# 17_CAN_BUS.net
KiCad netlist of a schematic drawn in Altium Designer
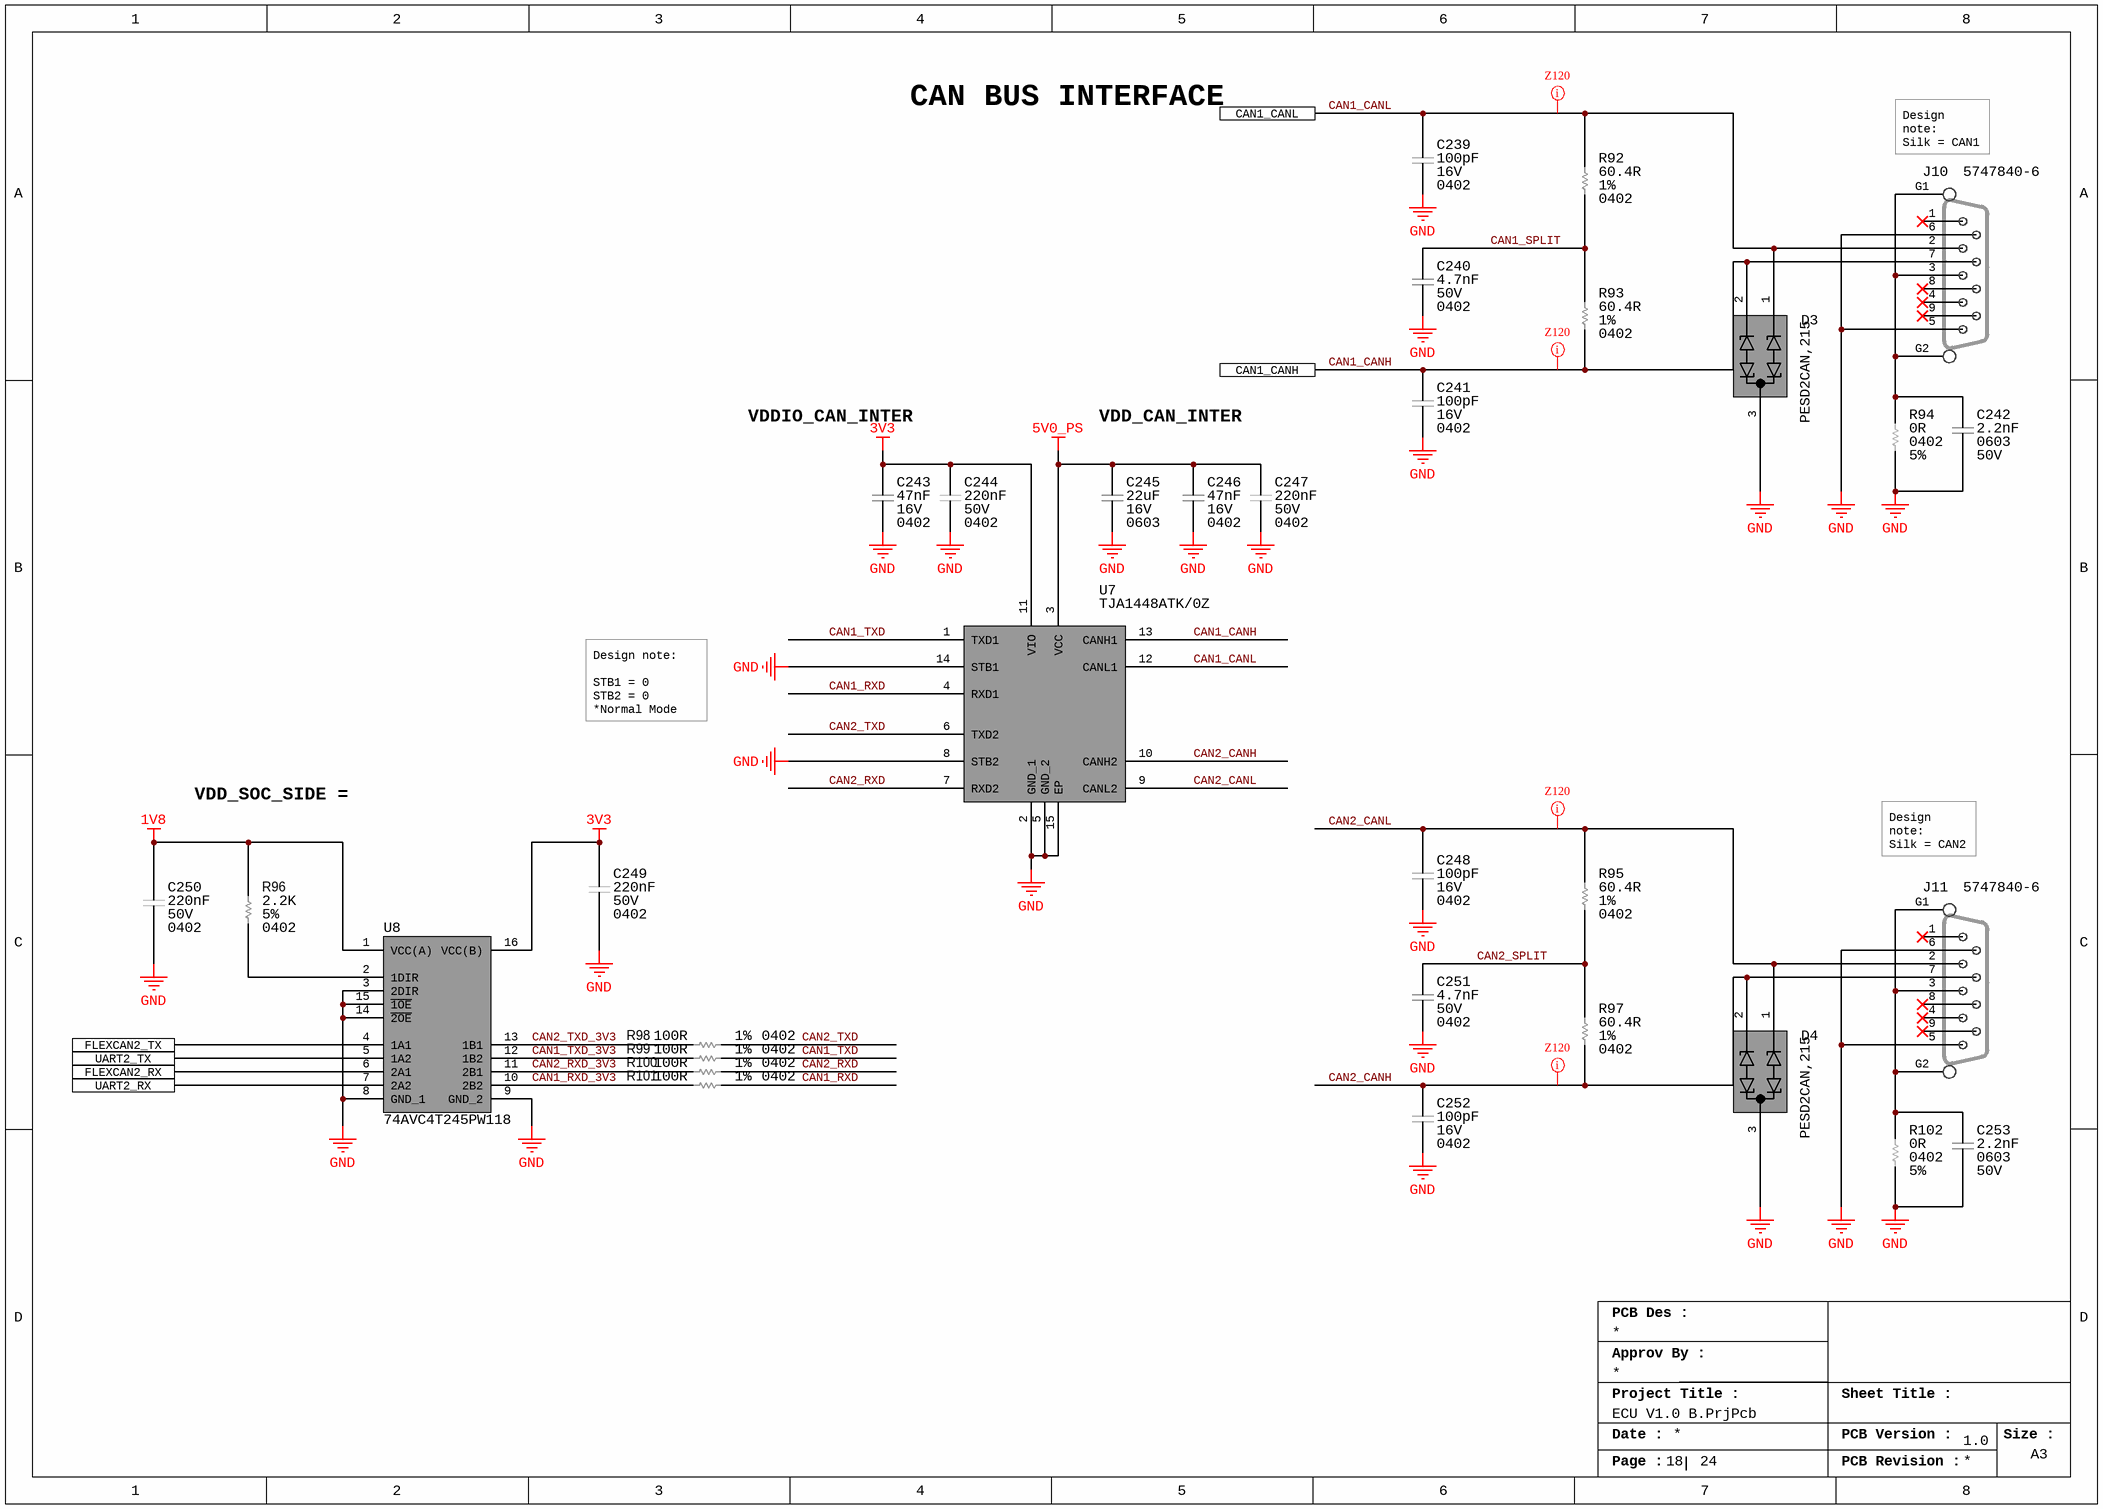
[diagram p0: 17_CAN_BUS.SchDoc]

(export (version "E")
  (design (tool "Eeschema 10.0.6"))
  (components
    (comp (ref "C239")
      (value "CC0402JRNPO7BN101")
      (footprint "CAP_0402_CAPC1005X05N")
      (description "0402 100 pF 16 V ±5 % Tolerance NP0 SMT Multilayer Ceramic Capacitor")
      (fields
        (field (name "MANUFACTURER") "Yageo")
        (field (name "TOLERANCE") "5%")
        (field (name "VOLTAGE RATING (DC)") "16V")
        (field (name "CAPACITANCE") "100pF")
        (field (name "CASE/PACKAGE") "0402")
      )
      (libsource (lib "Electronic Devices_LIB") (part "CAP_100PF_16V_NP0_0402"))
    )
    (comp (ref "C240")
      (value "GRM155R61H472KA01D")
      (footprint "CAP_0402_CAPC1005X05N")
      (description "Multilayer Ceramic Capacitor, 100 uF, 16 V, ± 20%, X5R, 1210 [3225 Metric]")
      (fields
        (field (name "MANUFACTURER") "Murata")
        (field (name "TOLERANCE") "10%")
        (field (name "VOLTAGE RATING") "50V")
        (field (name "CAPACITANCE") "4.7nF")
        (field (name "CASE/PACKAGE") "0402")
      )
      (libsource (lib "Electronic Devices_LIB") (part "CAP_4700PF_50V_X5R_0402"))
    )
    (comp (ref "C241")
      (value "CC0402JRNPO7BN101")
      (footprint "CAP_0402_CAPC1005X05N")
      (description "0402 100 pF 16 V ±5 % Tolerance NP0 SMT Multilayer Ceramic Capacitor")
      (fields
        (field (name "MANUFACTURER") "Yageo")
        (field (name "TOLERANCE") "5%")
        (field (name "VOLTAGE RATING (DC)") "16V")
        (field (name "CAPACITANCE") "100pF")
        (field (name "CASE/PACKAGE") "0402")
      )
      (libsource (lib "Electronic Devices_LIB") (part "CAP_100PF_16V_NP0_0402"))
    )
    (comp (ref "C242")
      (value "GRM1885C1H222JA01D")
      (footprint "CAP_0603_CAPC1608X08N")
      (description "Multilayer Ceramic Capacitor, 2200 pF, 50 V, ï¿½ 5%, C0G (NP0), 0603 [1608 Metric]")
      (fields
        (field (name "MANUFACTURER") "Murata")
        (field (name "TOLERANCE") "5%")
        (field (name "CASE/PACKAGE") "0603")
        (field (name "VOLTAGE RATING") "50V")
        (field (name "CAPACITANCE") "2.2nF")
      )
      (libsource (lib "Electronic Devices_LIB") (part "CAP_2.2nF_50V_NP0_0402"))
    )
    (comp (ref "C243")
      (value "GCM155R71C473KA37D")
      (footprint "CAP_0402_CAPC1005X05N")
      (description "Multilayer Ceramic Capacitor, 0.047 uF, 16 V, ± 10%, X7R, 0402 [1005 Metric]")
      (fields
        (field (name "MANUFACTURER") "Murata")
        (field (name "TOLERANCE") "10%")
        (field (name "CAPACITANCE") "47nF")
        (field (name "VOLTAGE RATING") "16V")
        (field (name "CASE/PACKAGE") "0402")
      )
      (libsource (lib "Electronic Devices_LIB") (part "CAP_47nF_16V_X7R_0402"))
    )
    (comp (ref "C244")
      (value "GRM155R61H224KE01W")
      (footprint "CAP_0402_CAPC1005X05N")
      (description "Multilayer Ceramic Capacitor, 0.22 uF, 50 VDC, ± 10%, X5R, 0402 [1005 Metric]")
      (fields
        (field (name "MANUFACTURER") "Murata")
        (field (name "CASE/PACKAGE") "0402")
        (field (name "VOLTAGE RATING (DC)") "50V")
        (field (name "CAPACITANCE") "220nF")
      )
      (libsource (lib "Electronic Devices_LIB") (part "CAP_0.22UF_50V_X5R_0402"))
    )
    (comp (ref "C245")
      (value "CL10A226MO7JZNC")
      (footprint "CAP_0603_CAPC1608X08N")
      (description "Cap Ceramic 22uF 16V X5R 20% Pad SMD 0603 85C T/R")
      (fields
        (field (name "MANUFACTURER") "Samsung")
        (field (name "TOLERANCE") "20%")
        (field (name "CAPACITANCE") "22uF")
        (field (name "VOLTAGE RATING") "16V")
        (field (name "CASE/PACKAGE") "0603")
      )
      (libsource (lib "Electronic Devices_LIB") (part "CAP_22UF_16V_X5R_0603"))
    )
    (comp (ref "C246")
      (value "GCM155R71C473KA37D")
      (footprint "CAP_0402_CAPC1005X05N")
      (description "Multilayer Ceramic Capacitor, 0.047 uF, 16 V, ± 10%, X7R, 0402 [1005 Metric]")
      (fields
        (field (name "MANUFACTURER") "Murata")
        (field (name "TOLERANCE") "10%")
        (field (name "CAPACITANCE") "47nF")
        (field (name "VOLTAGE RATING") "16V")
        (field (name "CASE/PACKAGE") "0402")
      )
      (libsource (lib "Electronic Devices_LIB") (part "CAP_47nF_16V_X7R_0402"))
    )
    (comp (ref "C247")
      (value "GRM155R61H224KE01W")
      (footprint "CAP_0402_CAPC1005X05N")
      (description "Multilayer Ceramic Capacitor, 0.22 uF, 50 VDC, ± 10%, X5R, 0402 [1005 Metric]")
      (fields
        (field (name "MANUFACTURER") "Murata")
        (field (name "CASE/PACKAGE") "0402")
        (field (name "VOLTAGE RATING (DC)") "50V")
        (field (name "CAPACITANCE") "220nF")
      )
      (libsource (lib "Electronic Devices_LIB") (part "CAP_0.22UF_50V_X5R_0402"))
    )
    (comp (ref "C248")
      (value "CC0402JRNPO7BN101")
      (footprint "CAP_0402_CAPC1005X05N")
      (description "0402 100 pF 16 V ±5 % Tolerance NP0 SMT Multilayer Ceramic Capacitor")
      (fields
        (field (name "MANUFACTURER") "Yageo")
        (field (name "TOLERANCE") "5%")
        (field (name "VOLTAGE RATING (DC)") "16V")
        (field (name "CAPACITANCE") "100pF")
        (field (name "CASE/PACKAGE") "0402")
      )
      (libsource (lib "Electronic Devices_LIB") (part "CAP_100PF_16V_NP0_0402"))
    )
    (comp (ref "C249")
      (value "GRM155R61H224KE01W")
      (footprint "CAP_0402_CAPC1005X05N")
      (description "Multilayer Ceramic Capacitor, 0.22 uF, 50 VDC, ± 10%, X5R, 0402 [1005 Metric]")
      (fields
        (field (name "MANUFACTURER") "Murata")
        (field (name "CASE/PACKAGE") "0402")
        (field (name "VOLTAGE RATING (DC)") "50V")
        (field (name "CAPACITANCE") "220nF")
      )
      (libsource (lib "Electronic Devices_LIB") (part "CAP_0.22UF_50V_X5R_0402"))
    )
    (comp (ref "C250")
      (value "GRM155R61H224KE01W")
      (footprint "CAP_0402_CAPC1005X05N")
      (description "Multilayer Ceramic Capacitor, 0.22 uF, 50 VDC, ± 10%, X5R, 0402 [1005 Metric]")
      (fields
        (field (name "MANUFACTURER") "Murata")
        (field (name "CASE/PACKAGE") "0402")
        (field (name "VOLTAGE RATING (DC)") "50V")
        (field (name "CAPACITANCE") "220nF")
      )
      (libsource (lib "Electronic Devices_LIB") (part "CAP_0.22UF_50V_X5R_0402"))
    )
    (comp (ref "C251")
      (value "GRM155R61H472KA01D")
      (footprint "CAP_0402_CAPC1005X05N")
      (description "Multilayer Ceramic Capacitor, 100 uF, 16 V, ± 20%, X5R, 1210 [3225 Metric]")
      (fields
        (field (name "MANUFACTURER") "Murata")
        (field (name "TOLERANCE") "10%")
        (field (name "VOLTAGE RATING") "50V")
        (field (name "CAPACITANCE") "4.7nF")
        (field (name "CASE/PACKAGE") "0402")
      )
      (libsource (lib "Electronic Devices_LIB") (part "CAP_4700PF_50V_X5R_0402"))
    )
    (comp (ref "C252")
      (value "CC0402JRNPO7BN101")
      (footprint "CAP_0402_CAPC1005X05N")
      (description "0402 100 pF 16 V ±5 % Tolerance NP0 SMT Multilayer Ceramic Capacitor")
      (fields
        (field (name "MANUFACTURER") "Yageo")
        (field (name "TOLERANCE") "5%")
        (field (name "VOLTAGE RATING (DC)") "16V")
        (field (name "CAPACITANCE") "100pF")
        (field (name "CASE/PACKAGE") "0402")
      )
      (libsource (lib "Electronic Devices_LIB") (part "CAP_100PF_16V_NP0_0402"))
    )
    (comp (ref "C253")
      (value "GRM1885C1H222JA01D")
      (footprint "CAP_0603_CAPC1608X08N")
      (description "Multilayer Ceramic Capacitor, 2200 pF, 50 V, ï¿½ 5%, C0G (NP0), 0603 [1608 Metric]")
      (fields
        (field (name "MANUFACTURER") "Murata")
        (field (name "TOLERANCE") "5%")
        (field (name "CASE/PACKAGE") "0603")
        (field (name "VOLTAGE RATING") "50V")
        (field (name "CAPACITANCE") "2.2nF")
      )
      (libsource (lib "Electronic Devices_LIB") (part "CAP_2.2nF_50V_NP0_0402"))
    )
    (comp (ref "D3")
      (value "PESD2CAN,215")
      (footprint "DIO_PESD2CAN,215")
      (description "5A 230W 41V 26.2V Bidirectional 24V SOT-23 ESD and Surge Protection (TVS/ESD) ROHS")
      (fields (field (name "MANUFACTURER") "Nexperia"))
      (libsource (lib "Electronic Devices_LIB") (part "DIO_TVS_41V_5A_PESD2CAN,215"))
    )
    (comp (ref "D4")
      (value "PESD2CAN,215")
      (footprint "DIO_PESD2CAN,215")
      (description "5A 230W 41V 26.2V Bidirectional 24V SOT-23 ESD and Surge Protection (TVS/ESD) ROHS")
      (fields (field (name "MANUFACTURER") "Nexperia"))
      (libsource (lib "Electronic Devices_LIB") (part "DIO_TVS_41V_5A_PESD2CAN,215"))
    )
    (comp (ref "J10")
      (value "5747840-6")
      (footprint "TE_5747840-6")
      (description "D Subminiature Connector, 9 Contact(s), Male, 0.108 inch Pitch, Solder Terminal, #4-40, Plug")
      (fields (field (name "MANUFACTURER") "TE Connectivity"))
      (libsource (lib "Electronic Devices_LIB") (part "CONN_DB9_TEConnectivity_5747840-6"))
    )
    (comp (ref "J11")
      (value "5747840-6")
      (footprint "TE_5747840-6")
      (description "D Subminiature Connector, 9 Contact(s), Male, 0.108 inch Pitch, Solder Terminal, #4-40, Plug")
      (fields (field (name "MANUFACTURER") "TE Connectivity"))
      (libsource (lib "Electronic Devices_LIB") (part "CONN_DB9_TEConnectivity_5747840-6"))
    )
    (comp (ref "R92")
      (value "RK73H1ETTP60R4F")
      (footprint "RES_0402_RESC1005X04N")
      (description "Res Thick Film 0402 60.4 Ohm 1% 0.1W(1/10W) ±100ppm/C Pad SMD Automotive T/R")
      (fields
        (field (name "MANUFACTURER") "KOA Speer")
        (field (name "TOLERANCE") "1%")
        (field (name "RESISTANCE") "60.4R")
        (field (name "CASE/PACKAGE") "0402")
      )
      (libsource (lib "Electronic Devices_LIB") (part "RES_60.4R_1%_100mW_0402"))
    )
    (comp (ref "R93")
      (value "RK73H1ETTP60R4F")
      (footprint "RES_0402_RESC1005X04N")
      (description "Res Thick Film 0402 60.4 Ohm 1% 0.1W(1/10W) ±100ppm/C Pad SMD Automotive T/R")
      (fields
        (field (name "MANUFACTURER") "KOA Speer")
        (field (name "TOLERANCE") "1%")
        (field (name "RESISTANCE") "60.4R")
        (field (name "CASE/PACKAGE") "0402")
      )
      (libsource (lib "Electronic Devices_LIB") (part "RES_60.4R_1%_100mW_0402"))
    )
    (comp (ref "R94")
      (value "ERJ-2GE0R00X")
      (footprint "RES_0402_RESC1005X04N")
      (description "SMD Chip Resistor, Jumper, 0 ohm, 100 mW, 0402 [1005 Metric], Thick Film, General Purpose")
      (fields
        (field (name "MANUFACTURER") "Panasonic")
        (field (name "CASE CODE (IMPERIAL)") "0402")
        (field (name "TOLERANCE") "5%")
        (field (name "RESISTANCE") "0R")
      )
      (libsource (lib "Electronic Devices_LIB") (part "RES_0R_5%_100mW_0402"))
    )
    (comp (ref "R95")
      (value "RK73H1ETTP60R4F")
      (footprint "RES_0402_RESC1005X04N")
      (description "Res Thick Film 0402 60.4 Ohm 1% 0.1W(1/10W) ±100ppm/C Pad SMD Automotive T/R")
      (fields
        (field (name "MANUFACTURER") "KOA Speer")
        (field (name "TOLERANCE") "1%")
        (field (name "RESISTANCE") "60.4R")
        (field (name "CASE/PACKAGE") "0402")
      )
      (libsource (lib "Electronic Devices_LIB") (part "RES_60.4R_1%_100mW_0402"))
    )
    (comp (ref "R96")
      (value "RC0402JR-072K2L")
      (footprint "RES_0402_RESC1005X04N")
      (description "SMD Chip Resistor, 2.2 kOhm, ± 5%, 63 mW, 0402 [1005 Metric], Thick Film, General Purpose")
      (fields
        (field (name "MANUFACTURER") "Yageo")
        (field (name "TOLERANCE") "5%")
        (field (name "RESISTANCE") "2.2K")
        (field (name "CASE/PACKAGE") "0402")
      )
      (libsource (lib "Electronic Devices_LIB") (part "RES_2.2K_5%_63mW_0402"))
    )
    (comp (ref "R97")
      (value "RK73H1ETTP60R4F")
      (footprint "RES_0402_RESC1005X04N")
      (description "Res Thick Film 0402 60.4 Ohm 1% 0.1W(1/10W) ±100ppm/C Pad SMD Automotive T/R")
      (fields
        (field (name "MANUFACTURER") "KOA Speer")
        (field (name "TOLERANCE") "1%")
        (field (name "RESISTANCE") "60.4R")
        (field (name "CASE/PACKAGE") "0402")
      )
      (libsource (lib "Electronic Devices_LIB") (part "RES_60.4R_1%_100mW_0402"))
    )
    (comp (ref "R98")
      (value "ERJ-2RKF1000X")
      (footprint "RES_0402_RESC1005X04N")
      (description "Resistor Thick Film 0402 100 Ohm 1% 1/10W 100ppm/C Molded SMD Punched Carrier T/R")
      (fields
        (field (name "MANUFACTURER") "Panasonic")
        (field (name "TOLERANCE") "1%")
        (field (name "RESISTANCE") "100R")
        (field (name "CASE/PACKAGE") "0402")
      )
      (libsource (lib "Electronic Devices_LIB") (part "RES_100R_1%_100mW_0402"))
    )
    (comp (ref "R99")
      (value "ERJ-2RKF1000X")
      (footprint "RES_0402_RESC1005X04N")
      (description "Resistor Thick Film 0402 100 Ohm 1% 1/10W 100ppm/C Molded SMD Punched Carrier T/R")
      (fields
        (field (name "MANUFACTURER") "Panasonic")
        (field (name "TOLERANCE") "1%")
        (field (name "RESISTANCE") "100R")
        (field (name "CASE/PACKAGE") "0402")
      )
      (libsource (lib "Electronic Devices_LIB") (part "RES_100R_1%_100mW_0402"))
    )
    (comp (ref "R100")
      (value "ERJ-2RKF1000X")
      (footprint "RES_0402_RESC1005X04N")
      (description "Resistor Thick Film 0402 100 Ohm 1% 1/10W 100ppm/C Molded SMD Punched Carrier T/R")
      (fields
        (field (name "MANUFACTURER") "Panasonic")
        (field (name "TOLERANCE") "1%")
        (field (name "RESISTANCE") "100R")
        (field (name "CASE/PACKAGE") "0402")
      )
      (libsource (lib "Electronic Devices_LIB") (part "RES_100R_1%_100mW_0402"))
    )
    (comp (ref "R101")
      (value "ERJ-2RKF1000X")
      (footprint "RES_0402_RESC1005X04N")
      (description "Resistor Thick Film 0402 100 Ohm 1% 1/10W 100ppm/C Molded SMD Punched Carrier T/R")
      (fields
        (field (name "MANUFACTURER") "Panasonic")
        (field (name "TOLERANCE") "1%")
        (field (name "RESISTANCE") "100R")
        (field (name "CASE/PACKAGE") "0402")
      )
      (libsource (lib "Electronic Devices_LIB") (part "RES_100R_1%_100mW_0402"))
    )
    (comp (ref "R102")
      (value "ERJ-2GE0R00X")
      (footprint "RES_0402_RESC1005X04N")
      (description "SMD Chip Resistor, Jumper, 0 ohm, 100 mW, 0402 [1005 Metric], Thick Film, General Purpose")
      (fields
        (field (name "MANUFACTURER") "Panasonic")
        (field (name "CASE CODE (IMPERIAL)") "0402")
        (field (name "TOLERANCE") "5%")
        (field (name "RESISTANCE") "0R")
      )
      (libsource (lib "Electronic Devices_LIB") (part "RES_0R_5%_100mW_0402"))
    )
    (comp (ref "U7")
      (value "TJA1448ATK/0Z")
      (footprint "SON65P300X450X100-15N")
      (description "Can Transceiver with Standby Mode Dual High-Speed 5Mbps 4.5V to 5.5V 14-Pin HVSON")
      (fields (field (name "MANUFACTURER") "NXP Semiconductors"))
      (libsource (lib "Electronic Devices_LIB") (part "IC_TRANSCEIVER_CAN_TJA1448ATK/0Z"))
    )
    (comp (ref "U8")
      (value "74AVC4T245PW118")
      (footprint "SOP65P640X110-16N")
      (description "74Avc4T245Pw/Sot403/Tssop16 Rohs Compliant: Yes ¦Nexperia 74AVC4T245PW 118")
      (fields (field (name "MANUFACTURER") "Nexperia"))
      (libsource (lib "Electronic Devices_LIB") (part "IC_TRANSLATION_TXRX_74AVC4T245PW118"))
    )
  )
  (nets
    (net (code "1") (name "/CAN1_CANH") (class "Default")
      (node (ref "C241") (pin "2") (pinfunction "2_2") (pintype "passive"))
      (node (ref "D3") (pin "2") (pinfunction "C2_2") (pintype "passive"))
      (node (ref "J10") (pin "7") (pinfunction "7_7") (pintype "passive"))
      (node (ref "R93") (pin "1") (pinfunction "1_1") (pintype "passive"))
      (node (ref "U7") (pin "13") (pinfunction "CANH1_13") (pintype "passive"))
    )
    (net (code "2") (name "/CAN1_CANL") (class "Default")
      (node (ref "C239") (pin "2") (pinfunction "2_2") (pintype "passive"))
      (node (ref "D3") (pin "1") (pinfunction "C1_1") (pintype "passive"))
      (node (ref "J10") (pin "2") (pinfunction "2_2") (pintype "passive"))
      (node (ref "R92") (pin "2") (pinfunction "2_2") (pintype "passive"))
      (node (ref "U7") (pin "12") (pinfunction "CANL1_12") (pintype "passive"))
    )
    (net (code "3") (name "/CAN1_RXD") (class "Default")
      (node (ref "R101") (pin "2") (pinfunction "2_2") (pintype "passive"))
      (node (ref "U7") (pin "4") (pinfunction "RXD1_4") (pintype "passive"))
    )
    (net (code "4") (name "/CAN1_RXD_3V3") (class "Default")
      (node (ref "R101") (pin "1") (pinfunction "1_1") (pintype "passive"))
      (node (ref "U8") (pin "10") (pinfunction "2B2_10") (pintype "passive"))
    )
    (net (code "5") (name "/CAN1_SPLIT") (class "Default")
      (node (ref "C240") (pin "2") (pinfunction "2_2") (pintype "passive"))
      (node (ref "R92") (pin "1") (pinfunction "1_1") (pintype "passive"))
      (node (ref "R93") (pin "2") (pinfunction "2_2") (pintype "passive"))
    )
    (net (code "6") (name "/CAN1_TXD") (class "Default")
      (node (ref "R99") (pin "2") (pinfunction "2_2") (pintype "passive"))
      (node (ref "U7") (pin "1") (pinfunction "TXD1_1") (pintype "passive"))
    )
    (net (code "7") (name "/CAN1_TXD_3V3") (class "Default")
      (node (ref "R99") (pin "1") (pinfunction "1_1") (pintype "passive"))
      (node (ref "U8") (pin "12") (pinfunction "1B2_12") (pintype "passive"))
    )
    (net (code "8") (name "/CAN2_CANH") (class "Default")
      (node (ref "C252") (pin "2") (pinfunction "2_2") (pintype "passive"))
      (node (ref "D4") (pin "2") (pinfunction "C2_2") (pintype "passive"))
      (node (ref "J11") (pin "7") (pinfunction "7_7") (pintype "passive"))
      (node (ref "R97") (pin "1") (pinfunction "1_1") (pintype "passive"))
      (node (ref "U7") (pin "10") (pinfunction "CANH2_10") (pintype "passive"))
    )
    (net (code "9") (name "/CAN2_CANL") (class "Default")
      (node (ref "C248") (pin "2") (pinfunction "2_2") (pintype "passive"))
      (node (ref "D4") (pin "1") (pinfunction "C1_1") (pintype "passive"))
      (node (ref "J11") (pin "2") (pinfunction "2_2") (pintype "passive"))
      (node (ref "R95") (pin "2") (pinfunction "2_2") (pintype "passive"))
      (node (ref "U7") (pin "9") (pinfunction "CANL2_9") (pintype "passive"))
    )
    (net (code "10") (name "/CAN2_RXD") (class "Default")
      (node (ref "R100") (pin "2") (pinfunction "2_2") (pintype "passive"))
      (node (ref "U7") (pin "7") (pinfunction "RXD2_7") (pintype "passive"))
    )
    (net (code "11") (name "/CAN2_RXD_3V3") (class "Default")
      (node (ref "R100") (pin "1") (pinfunction "1_1") (pintype "passive"))
      (node (ref "U8") (pin "11") (pinfunction "2B1_11") (pintype "passive"))
    )
    (net (code "12") (name "/CAN2_SPLIT") (class "Default")
      (node (ref "C251") (pin "2") (pinfunction "2_2") (pintype "passive"))
      (node (ref "R95") (pin "1") (pinfunction "1_1") (pintype "passive"))
      (node (ref "R97") (pin "2") (pinfunction "2_2") (pintype "passive"))
    )
    (net (code "13") (name "/CAN2_TXD") (class "Default")
      (node (ref "R98") (pin "2") (pinfunction "2_2") (pintype "passive"))
      (node (ref "U7") (pin "6") (pinfunction "TXD2_6") (pintype "passive"))
    )
    (net (code "14") (name "/CAN2_TXD_3V3") (class "Default")
      (node (ref "R98") (pin "1") (pinfunction "1_1") (pintype "passive"))
      (node (ref "U8") (pin "13") (pinfunction "1B1_13") (pintype "passive"))
    )
    (net (code "15") (name "/FLEXCAN2_RX") (class "Default")
      (node (ref "U8") (pin "6") (pinfunction "2A1_6") (pintype "passive"))
    )
    (net (code "16") (name "/FLEXCAN2_TX") (class "Default")
      (node (ref "U8") (pin "4") (pinfunction "1A1_4") (pintype "passive"))
    )
    (net (code "17") (name "/UART2_RX") (class "Default")
      (node (ref "U8") (pin "7") (pinfunction "2A2_7") (pintype "passive"))
    )
    (net (code "18") (name "/UART2_TX") (class "Default")
      (node (ref "U8") (pin "5") (pinfunction "1A2_5") (pintype "passive"))
    )
    (net (code "19") (name "1V8") (class "Default")
      (node (ref "C250") (pin "2") (pinfunction "2_2") (pintype "passive"))
      (node (ref "R96") (pin "2") (pinfunction "2_2") (pintype "passive"))
      (node (ref "U8") (pin "1") (pinfunction "VCC(A)_1") (pintype "passive"))
    )
    (net (code "20") (name "3V3") (class "Default")
      (node (ref "C243") (pin "2") (pinfunction "2_2") (pintype "passive"))
      (node (ref "C244") (pin "1") (pinfunction "1_1") (pintype "passive"))
      (node (ref "C249") (pin "2") (pinfunction "2_2") (pintype "passive"))
      (node (ref "U7") (pin "11") (pinfunction "VIO_11") (pintype "passive"))
      (node (ref "U8") (pin "16") (pinfunction "VCC(B)_16") (pintype "passive"))
    )
    (net (code "21") (name "5V0_PS") (class "Default")
      (node (ref "C245") (pin "2") (pinfunction "2_2") (pintype "passive"))
      (node (ref "C246") (pin "2") (pinfunction "2_2") (pintype "passive"))
      (node (ref "C247") (pin "1") (pinfunction "1_1") (pintype "passive"))
      (node (ref "U7") (pin "3") (pinfunction "VCC_3") (pintype "passive"))
    )
    (net (code "22") (name "GND") (class "Default")
      (node (ref "C239") (pin "1") (pinfunction "1_1") (pintype "passive"))
      (node (ref "C240") (pin "1") (pinfunction "1_1") (pintype "passive"))
      (node (ref "C241") (pin "1") (pinfunction "1_1") (pintype "passive"))
      (node (ref "C242") (pin "1") (pinfunction "1_1") (pintype "passive"))
      (node (ref "C243") (pin "1") (pinfunction "1_1") (pintype "passive"))
      (node (ref "C244") (pin "2") (pinfunction "2_2") (pintype "passive"))
      (node (ref "C245") (pin "1") (pinfunction "1_1") (pintype "passive"))
      (node (ref "C246") (pin "1") (pinfunction "1_1") (pintype "passive"))
      (node (ref "C247") (pin "2") (pinfunction "2_2") (pintype "passive"))
      (node (ref "C248") (pin "1") (pinfunction "1_1") (pintype "passive"))
      (node (ref "C249") (pin "1") (pinfunction "1_1") (pintype "passive"))
      (node (ref "C250") (pin "1") (pinfunction "1_1") (pintype "passive"))
      (node (ref "C251") (pin "1") (pinfunction "1_1") (pintype "passive"))
      (node (ref "C252") (pin "1") (pinfunction "1_1") (pintype "passive"))
      (node (ref "C253") (pin "1") (pinfunction "1_1") (pintype "passive"))
      (node (ref "D3") (pin "3") (pinfunction "CC_3") (pintype "passive"))
      (node (ref "D4") (pin "3") (pinfunction "CC_3") (pintype "passive"))
      (node (ref "J10") (pin "5") (pinfunction "5_5") (pintype "passive"))
      (node (ref "J10") (pin "6") (pinfunction "6_6") (pintype "passive"))
      (node (ref "J11") (pin "5") (pinfunction "5_5") (pintype "passive"))
      (node (ref "J11") (pin "6") (pinfunction "6_6") (pintype "passive"))
      (node (ref "R102") (pin "1") (pinfunction "1_1") (pintype "passive"))
      (node (ref "R94") (pin "1") (pinfunction "1_1") (pintype "passive"))
      (node (ref "U7") (pin "14") (pinfunction "STB1_14") (pintype "passive"))
      (node (ref "U7") (pin "15") (pinfunction "EP_15") (pintype "passive"))
      (node (ref "U7") (pin "2") (pinfunction "GND_1_2") (pintype "passive"))
      (node (ref "U7") (pin "5") (pinfunction "GND_2_5") (pintype "passive"))
      (node (ref "U7") (pin "8") (pinfunction "STB2_8") (pintype "passive"))
      (node (ref "U8") (pin "14") (pinfunction "~{2OE}_14") (pintype "passive"))
      (node (ref "U8") (pin "15") (pinfunction "~{1OE}_15") (pintype "passive"))
      (node (ref "U8") (pin "3") (pinfunction "2DIR_3") (pintype "passive"))
      (node (ref "U8") (pin "8") (pinfunction "GND_1_8") (pintype "passive"))
      (node (ref "U8") (pin "9") (pinfunction "GND_2_9") (pintype "passive"))
    )
    (net (code "23") (name "Net-(J10-G)") (class "Default")
      (node (ref "C242") (pin "2") (pinfunction "2_2") (pintype "passive"))
      (node (ref "J10") (pin "3") (pinfunction "3_3") (pintype "passive"))
      (node (ref "J10") (pin "G1") (pinfunction "G1_G1") (pintype "passive"))
      (node (ref "J10") (pin "G2") (pinfunction "G_G2") (pintype "passive"))
      (node (ref "R94") (pin "2") (pinfunction "2_2") (pintype "passive"))
    )
    (net (code "24") (name "Net-(J11-G)") (class "Default")
      (node (ref "C253") (pin "2") (pinfunction "2_2") (pintype "passive"))
      (node (ref "J11") (pin "3") (pinfunction "3_3") (pintype "passive"))
      (node (ref "J11") (pin "G1") (pinfunction "G1_G1") (pintype "passive"))
      (node (ref "J11") (pin "G2") (pinfunction "G_G2") (pintype "passive"))
      (node (ref "R102") (pin "2") (pinfunction "2_2") (pintype "passive"))
    )
    (net (code "25") (name "Net-(U8-1DIR)") (class "Default")
      (node (ref "R96") (pin "1") (pinfunction "1_1") (pintype "passive"))
      (node (ref "U8") (pin "2") (pinfunction "1DIR_2") (pintype "passive"))
    )
    (net (code "26") (name "unconnected-(J10-Pad1)") (class "Default")
      (node (ref "J10") (pin "1") (pinfunction "1_1") (pintype "passive+no_connect"))
    )
    (net (code "27") (name "unconnected-(J10-Pad4)") (class "Default")
      (node (ref "J10") (pin "4") (pinfunction "4_4") (pintype "passive+no_connect"))
    )
    (net (code "28") (name "unconnected-(J10-Pad8)") (class "Default")
      (node (ref "J10") (pin "8") (pinfunction "8_8") (pintype "passive+no_connect"))
    )
    (net (code "29") (name "unconnected-(J10-Pad9)") (class "Default")
      (node (ref "J10") (pin "9") (pinfunction "9_9") (pintype "passive+no_connect"))
    )
    (net (code "30") (name "unconnected-(J11-Pad1)") (class "Default")
      (node (ref "J11") (pin "1") (pinfunction "1_1") (pintype "passive+no_connect"))
    )
    (net (code "31") (name "unconnected-(J11-Pad4)") (class "Default")
      (node (ref "J11") (pin "4") (pinfunction "4_4") (pintype "passive+no_connect"))
    )
    (net (code "32") (name "unconnected-(J11-Pad8)") (class "Default")
      (node (ref "J11") (pin "8") (pinfunction "8_8") (pintype "passive+no_connect"))
    )
    (net (code "33") (name "unconnected-(J11-Pad9)") (class "Default")
      (node (ref "J11") (pin "9") (pinfunction "9_9") (pintype "passive+no_connect"))
    )
  )
)
